# Button-Sensor.net
KiCad netlist of a schematic drawn in Altium Designer
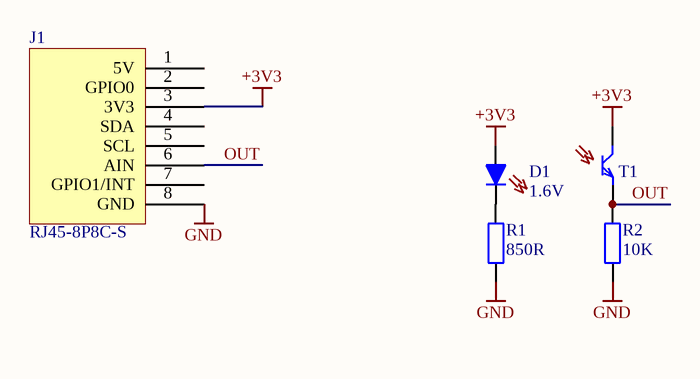
[diagram p0: Button-Sensor.SchDoc]

(export (version "E")
  (design (tool "Eeschema 10.0.6"))
  (components
    (comp (ref "D1")
      (value "1.6V")
      (footprint "LTE302")
      (description "IR LED 940nm")
      (libsource (lib "Bumper") (part "LTE-302"))
    )
    (comp (ref "J1")
      (value "RJ45-8P8C-S")
      (footprint "RJ45-8P8C")
      (libsource (lib "Bumper") (part "RJ45-8P8C-S"))
    )
    (comp (ref "R1")
      (value "850R")
      (footprint "RESC1608X06M")
      (libsource (lib "Bumper") (part "Resistor 850"))
    )
    (comp (ref "R2")
      (value "10K")
      (footprint "RESC1608X06M")
      (libsource (lib "Bumper") (part "Resistor 10K"))
    )
    (comp (ref "T1")
      (value "LTR301")
      (footprint "LTR301")
      (description "Phototransistor 940nm")
      (libsource (lib "Bumper") (part "LTR301"))
    )
  )
  (nets
    (net (code "1") (name "+3V3") (class "Default")
      (node (ref "D1") (pin "1") (pinfunction "A_1") (pintype "passive"))
      (node (ref "J1") (pin "3") (pinfunction "3V3_3") (pintype "passive"))
      (node (ref "T1") (pin "2") (pinfunction "E_2") (pintype "passive"))
    )
    (net (code "2") (name "/OUT") (class "Default")
      (node (ref "J1") (pin "6") (pinfunction "AIN_6") (pintype "passive"))
      (node (ref "R2") (pin "2") (pinfunction "2_2") (pintype "passive"))
      (node (ref "T1") (pin "1") (pinfunction "C_1") (pintype "passive"))
    )
    (net (code "3") (name "GND") (class "Default")
      (node (ref "J1") (pin "8") (pinfunction "GND_8") (pintype "passive"))
      (node (ref "R1") (pin "1") (pinfunction "1_1") (pintype "passive"))
      (node (ref "R2") (pin "1") (pinfunction "1_1") (pintype "passive"))
    )
    (net (code "4") (name "Net-(D1-K)") (class "Default")
      (node (ref "D1") (pin "2") (pinfunction "K_2") (pintype "passive"))
      (node (ref "R1") (pin "2") (pinfunction "2_2") (pintype "passive"))
    )
    (net (code "5") (name "unconnected-(J1-5V-Pad1)") (class "Default")
      (node (ref "J1") (pin "1") (pinfunction "5V_1") (pintype "passive"))
    )
    (net (code "6") (name "unconnected-(J1-GPIO0-Pad2)") (class "Default")
      (node (ref "J1") (pin "2") (pinfunction "GPIO0_2") (pintype "passive"))
    )
    (net (code "7") (name "unconnected-(J1-GPIO1{slash}INT-Pad7)") (class "Default")
      (node (ref "J1") (pin "7") (pinfunction "GPIO1/INT_7") (pintype "passive"))
    )
    (net (code "8") (name "unconnected-(J1-SCL-Pad5)") (class "Default")
      (node (ref "J1") (pin "5") (pinfunction "SCL_5") (pintype "passive"))
    )
    (net (code "9") (name "unconnected-(J1-SDA-Pad4)") (class "Default")
      (node (ref "J1") (pin "4") (pinfunction "SDA_4") (pintype "passive"))
    )
  )
)
